# Sheet1.net
KiCad netlist of a schematic drawn in Altium Designer
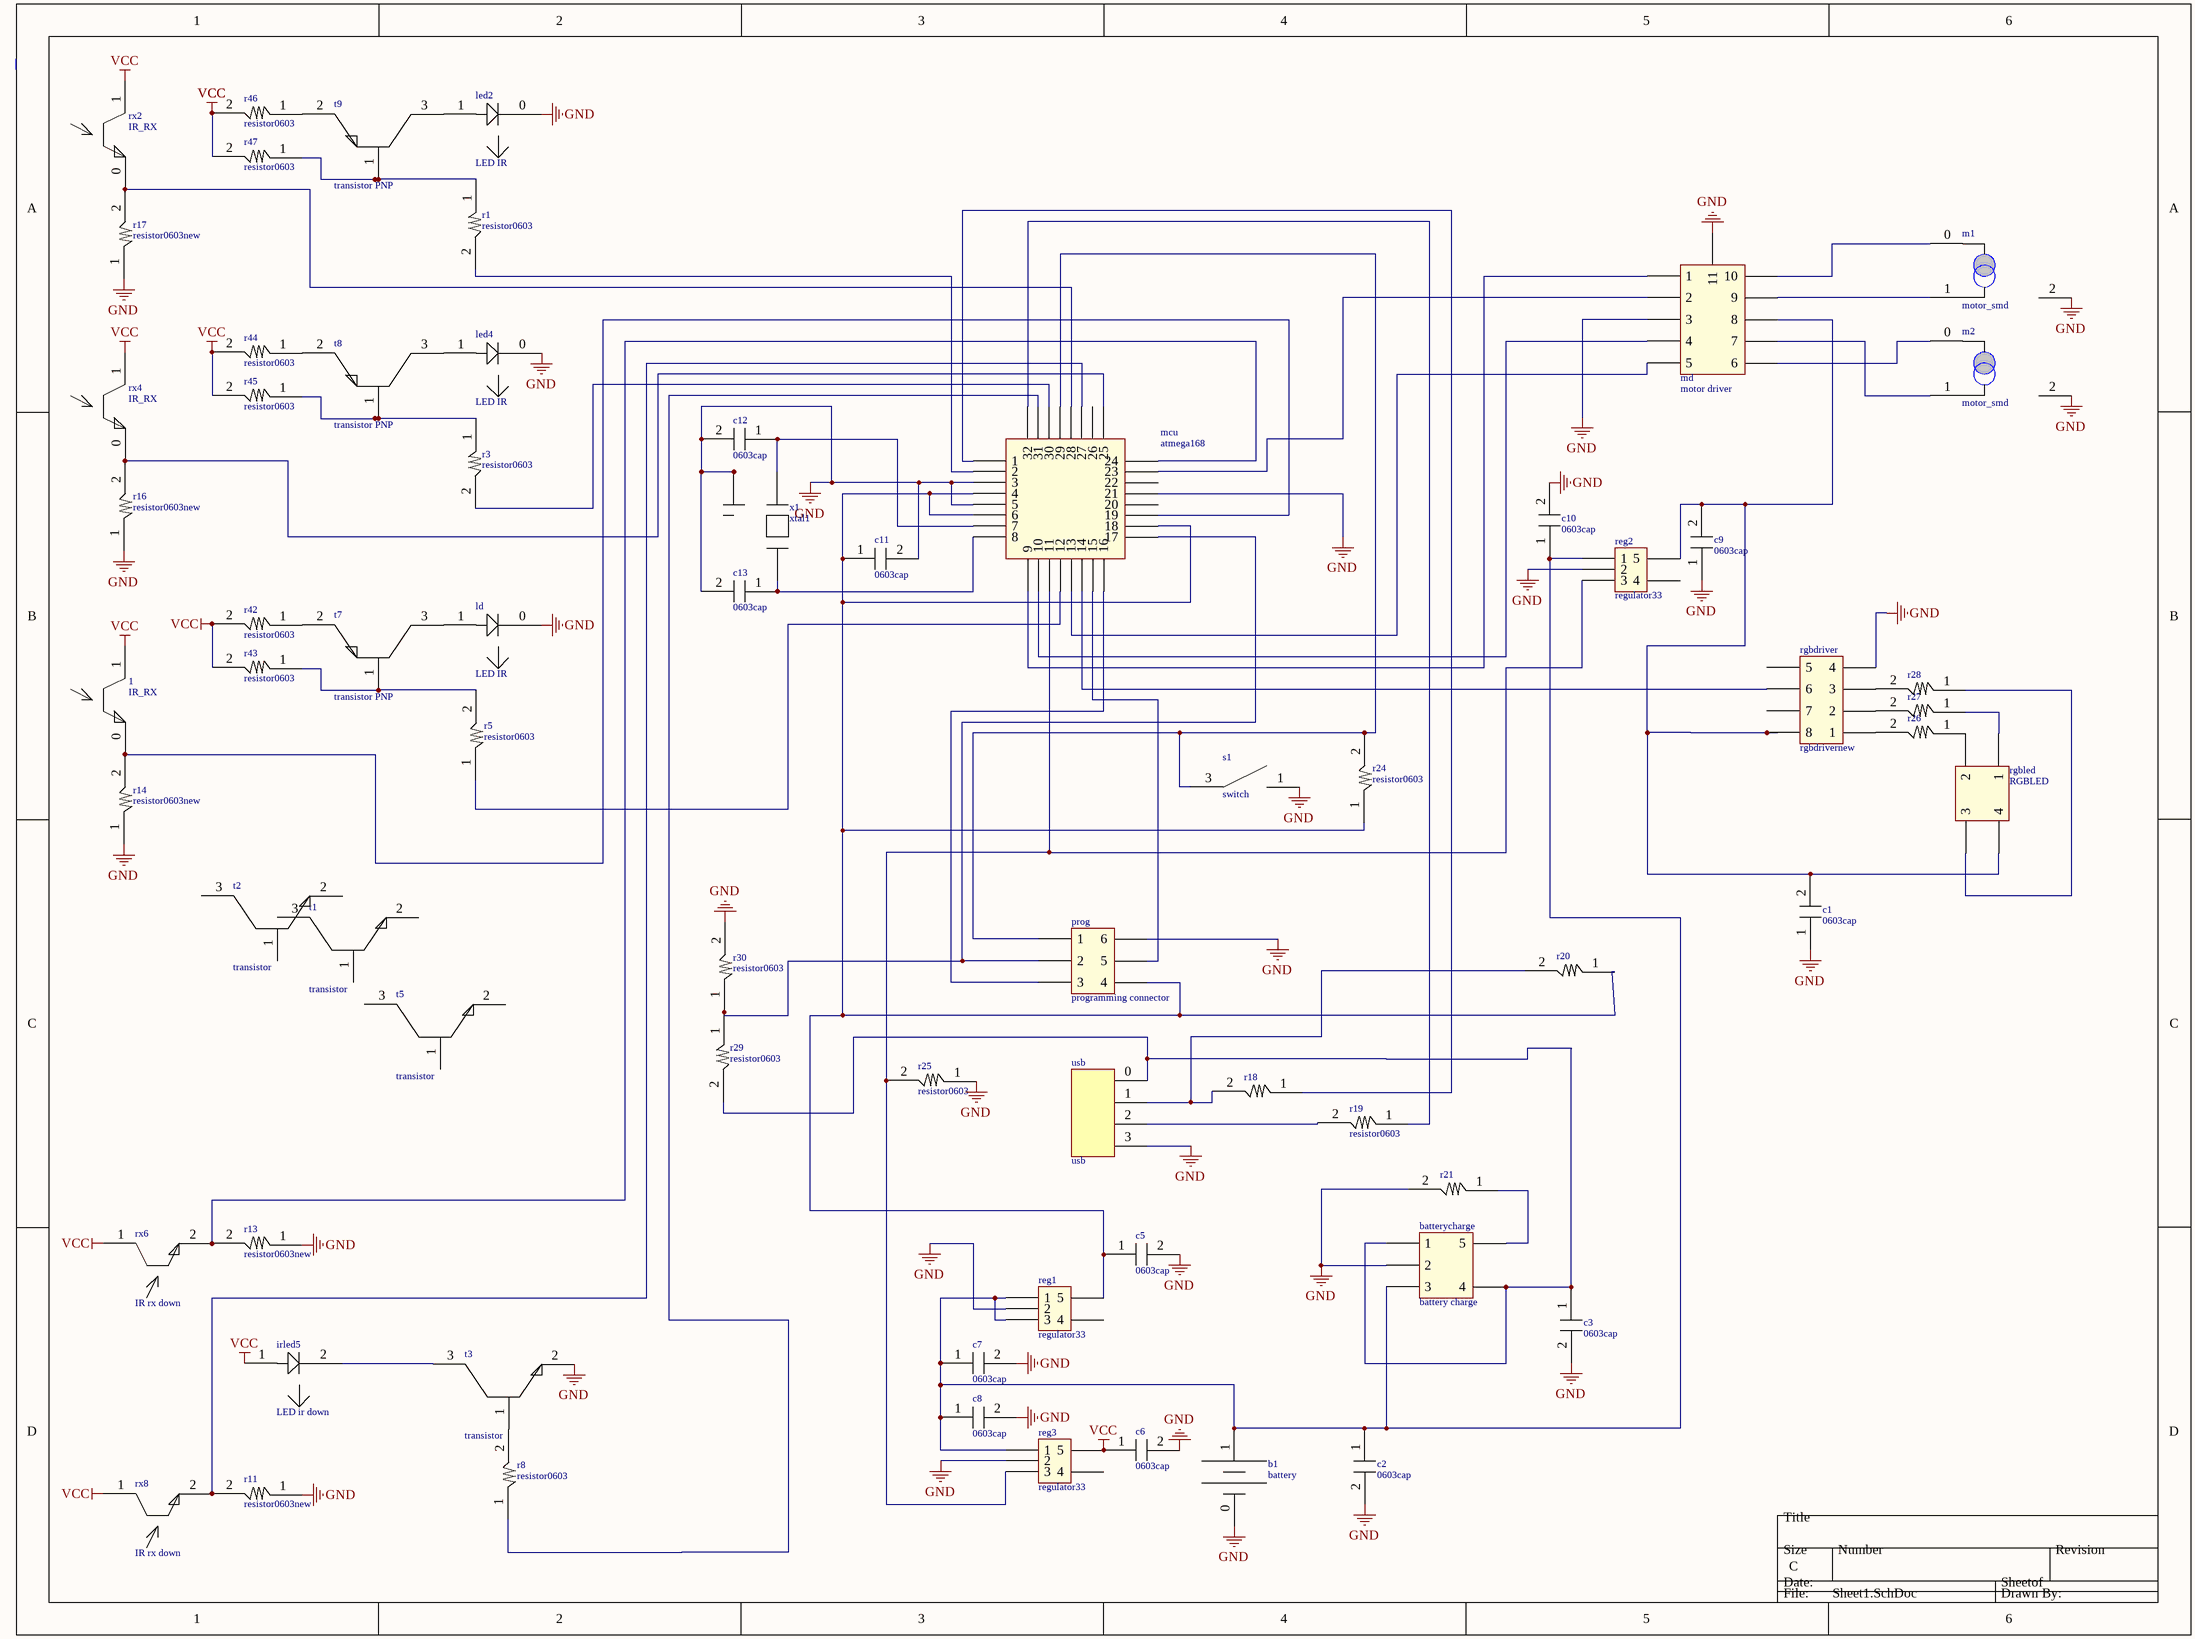
[diagram p0: Sheet1.SchDoc]

(export (version "E")
  (design (tool "Eeschema 10.0.6"))
  (components
    (comp (ref "1") (value "IR_RX") (footprint "ir sensor") (libsource (lib "Schlib1") (part "IR_RX")))
    (comp (ref "b1") (value "battery") (footprint "battery") (libsource (lib "Schlib1") (part "battery")))
    (comp (ref "batterycharge")
      (value "battery charge")
      (footprint "Battery charger")
      (libsource (lib "Schlib1") (part "battery charge"))
    )
    (comp (ref "c1") (value "0603cap") (footprint "0603new") (libsource (lib "Schlib1") (part "0603cap")))
    (comp (ref "c2") (value "0603cap") (footprint "0603new") (libsource (lib "Schlib1") (part "0603cap")))
    (comp (ref "c3") (value "0603cap") (footprint "0603new") (libsource (lib "Schlib1") (part "0603cap")))
    (comp (ref "c5") (value "0603cap") (footprint "0603new") (libsource (lib "Schlib1") (part "0603cap")))
    (comp (ref "c6") (value "0603cap") (footprint "0603new") (libsource (lib "Schlib1") (part "0603cap")))
    (comp (ref "c7") (value "0603cap") (footprint "0603new") (libsource (lib "Schlib1") (part "0603cap")))
    (comp (ref "c8") (value "0603cap") (footprint "0603new") (libsource (lib "Schlib1") (part "0603cap")))
    (comp (ref "c9") (value "0603cap") (footprint "0603new") (libsource (lib "Schlib1") (part "0603cap")))
    (comp (ref "c10") (value "0603cap") (footprint "0603new") (libsource (lib "Schlib1") (part "0603cap")))
    (comp (ref "c11") (value "0603cap") (footprint "0603new") (libsource (lib "Schlib1") (part "0603cap")))
    (comp (ref "c12") (value "0603cap") (footprint "0603new") (libsource (lib "Schlib1") (part "0603cap")))
    (comp (ref "c13") (value "0603cap") (footprint "0603new") (libsource (lib "Schlib1") (part "0603cap")))
    (comp (ref "irled5")
      (value "LED ir down")
      (footprint "irdown")
      (libsource (lib "Schlib1") (part "LED ir down"))
    )
    (comp (ref "ld") (value "LED IR") (footprint "ir led") (libsource (lib "Schlib1") (part "LED IR")))
    (comp (ref "led2") (value "LED IR") (footprint "ir led") (libsource (lib "Schlib1") (part "LED IR")))
    (comp (ref "led4") (value "LED IR") (footprint "ir led") (libsource (lib "Schlib1") (part "LED IR")))
    (comp (ref "m1") (value "motor_smd") (footprint "motor") (libsource (lib "Schlib1") (part "motor_smd")))
    (comp (ref "m2") (value "motor_smd") (footprint "motor") (libsource (lib "Schlib1") (part "motor_smd")))
    (comp (ref "mcu")
      (value "atmega168")
      (footprint "32pintqfp")
      (libsource (lib "Schlib1") (part "atmega168"))
    )
    (comp (ref "md")
      (value "motor driver")
      (footprint "motor driver")
      (libsource (lib "Schlib1") (part "motor driver"))
    )
    (comp (ref "prog")
      (value "programming connector")
      (footprint "Program connector")
      (libsource (lib "Schlib1") (part "programming connector"))
    )
    (comp (ref "r1")
      (value "resistor0603")
      (footprint "0603new")
      (libsource (lib "Schlib1") (part "resistor0603"))
    )
    (comp (ref "r3")
      (value "resistor0603")
      (footprint "0603new")
      (libsource (lib "Schlib1") (part "resistor0603"))
    )
    (comp (ref "r5")
      (value "resistor0603")
      (footprint "0603new")
      (libsource (lib "Schlib1") (part "resistor0603"))
    )
    (comp (ref "r8")
      (value "resistor0603")
      (footprint "0603new")
      (libsource (lib "Schlib1") (part "resistor0603"))
    )
    (comp (ref "r11")
      (value "resistor0603new")
      (footprint "0603new")
      (libsource (lib "Schlib1") (part "resistor0603new"))
    )
    (comp (ref "r13")
      (value "resistor0603new")
      (footprint "0603new")
      (libsource (lib "") (part "resistor0603new_1"))
    )
    (comp (ref "r14")
      (value "resistor0603new")
      (footprint "0603new")
      (libsource (lib "") (part "resistor0603new_1"))
    )
    (comp (ref "r16")
      (value "resistor0603new")
      (footprint "0603new")
      (libsource (lib "") (part "resistor0603new_1"))
    )
    (comp (ref "r17")
      (value "resistor0603new")
      (footprint "0603new")
      (libsource (lib "") (part "resistor0603new_1"))
    )
    (comp (ref "r18")
      (value "resistor0603")
      (footprint "0603new")
      (libsource (lib "Schlib1") (part "resistor0603"))
    )
    (comp (ref "r19")
      (value "resistor0603")
      (footprint "0603new")
      (libsource (lib "Schlib1") (part "resistor0603"))
    )
    (comp (ref "r20")
      (value "resistor0603")
      (footprint "0603new")
      (libsource (lib "Schlib1") (part "resistor0603"))
    )
    (comp (ref "r21")
      (value "resistor0603")
      (footprint "0603new")
      (libsource (lib "Schlib1") (part "resistor0603"))
    )
    (comp (ref "r24")
      (value "resistor0603")
      (footprint "0603new")
      (libsource (lib "Schlib1") (part "resistor0603"))
    )
    (comp (ref "r25")
      (value "resistor0603")
      (footprint "0603new")
      (libsource (lib "Schlib1") (part "resistor0603"))
    )
    (comp (ref "r26")
      (value "resistor0603")
      (footprint "0603new")
      (libsource (lib "Schlib1") (part "resistor0603"))
    )
    (comp (ref "r27")
      (value "resistor0603")
      (footprint "0603new")
      (libsource (lib "Schlib1") (part "resistor0603"))
    )
    (comp (ref "r28")
      (value "resistor0603")
      (footprint "0603new")
      (libsource (lib "Schlib1") (part "resistor0603"))
    )
    (comp (ref "r29")
      (value "resistor0603")
      (footprint "0603new")
      (libsource (lib "Schlib1") (part "resistor0603"))
    )
    (comp (ref "r30")
      (value "resistor0603")
      (footprint "0603new")
      (libsource (lib "Schlib1") (part "resistor0603"))
    )
    (comp (ref "r42")
      (value "resistor0603")
      (footprint "0603new")
      (libsource (lib "Schlib1") (part "resistor0603"))
    )
    (comp (ref "r43")
      (value "resistor0603")
      (footprint "0603new")
      (libsource (lib "Schlib1") (part "resistor0603"))
    )
    (comp (ref "r44")
      (value "resistor0603")
      (footprint "0603new")
      (libsource (lib "Schlib1") (part "resistor0603"))
    )
    (comp (ref "r45")
      (value "resistor0603")
      (footprint "0603new")
      (libsource (lib "Schlib1") (part "resistor0603"))
    )
    (comp (ref "r46")
      (value "resistor0603")
      (footprint "0603new")
      (libsource (lib "Schlib1") (part "resistor0603"))
    )
    (comp (ref "r47")
      (value "resistor0603")
      (footprint "0603new")
      (libsource (lib "Schlib1") (part "resistor0603"))
    )
    (comp (ref "reg1")
      (value "regulator33")
      (footprint "regulator")
      (libsource (lib "Schlib1") (part "regulator33"))
    )
    (comp (ref "reg2")
      (value "regulator33")
      (footprint "regulator")
      (libsource (lib "Schlib1") (part "regulator33"))
    )
    (comp (ref "reg3")
      (value "regulator33")
      (footprint "regulator")
      (libsource (lib "Schlib1") (part "regulator33"))
    )
    (comp (ref "rgbdriver")
      (value "rgbdrivernew")
      (footprint "RGBdrivernew")
      (description "rgbdrver")
      (libsource (lib "Schlib1") (part "rgbdrivernew"))
    )
    (comp (ref "rgbled") (value "RGBLED") (footprint "rgbled") (libsource (lib "Schlib1") (part "RGBLED")))
    (comp (ref "rx2") (value "IR_RX") (footprint "ir sensor") (libsource (lib "Schlib1") (part "IR_RX")))
    (comp (ref "rx4") (value "IR_RX") (footprint "ir sensor") (libsource (lib "Schlib1") (part "IR_RX")))
    (comp (ref "rx6")
      (value "IR rx down")
      (footprint "irdown")
      (libsource (lib "Schlib1") (part "IR rx down"))
    )
    (comp (ref "rx8")
      (value "IR rx down")
      (footprint "irdown")
      (libsource (lib "Schlib1") (part "IR rx down"))
    )
    (comp (ref "s1") (value "switch") (footprint "switch") (libsource (lib "Schlib1") (part "switch")))
    (comp (ref "t1")
      (value "transistor")
      (footprint "transistor")
      (libsource (lib "Schlib1") (part "transistor"))
    )
    (comp (ref "t2")
      (value "transistor")
      (footprint "transistor")
      (libsource (lib "Schlib1") (part "transistor"))
    )
    (comp (ref "t3")
      (value "transistor")
      (footprint "transistor")
      (libsource (lib "Schlib1") (part "transistor"))
    )
    (comp (ref "t5")
      (value "transistor")
      (footprint "transistor")
      (libsource (lib "Schlib1") (part "transistor"))
    )
    (comp (ref "t7")
      (value "transistor PNP")
      (footprint "transistor")
      (libsource (lib "Schlib1") (part "transistor PNP"))
    )
    (comp (ref "t8")
      (value "transistor PNP")
      (footprint "transistor")
      (libsource (lib "Schlib1") (part "transistor PNP"))
    )
    (comp (ref "t9")
      (value "transistor PNP")
      (footprint "transistor")
      (libsource (lib "Schlib1") (part "transistor PNP"))
    )
    (comp (ref "usb") (value "usb") (footprint "usb") (libsource (lib "Schlib1") (part "usb")))
    (comp (ref "x1")
      (value "xtal1")
      (footprint "xtal1")
      (description "xtal")
      (libsource (lib "Schlib1") (part "xtal"))
    )
  )
  (nets
    (net (code "1") (name "GND") (class "Default")
      (node (ref "b1") (pin "0") (pinfunction "0_0") (pintype "passive"))
      (node (ref "batterycharge") (pin "2") (pinfunction "2_2") (pintype "passive"))
      (node (ref "c1") (pin "1") (pinfunction "1_1") (pintype "passive"))
      (node (ref "c10") (pin "2") (pinfunction "2_2") (pintype "passive"))
      (node (ref "c11") (pin "2") (pinfunction "2_2") (pintype "passive"))
      (node (ref "c12") (pin "2") (pinfunction "2_2") (pintype "passive"))
      (node (ref "c13") (pin "2") (pinfunction "2_2") (pintype "passive"))
      (node (ref "c2") (pin "2") (pinfunction "2_2") (pintype "passive"))
      (node (ref "c3") (pin "2") (pinfunction "2_2") (pintype "passive"))
      (node (ref "c5") (pin "2") (pinfunction "2_2") (pintype "passive"))
      (node (ref "c6") (pin "2") (pinfunction "2_2") (pintype "passive"))
      (node (ref "c7") (pin "2") (pinfunction "2_2") (pintype "passive"))
      (node (ref "c8") (pin "2") (pinfunction "2_2") (pintype "passive"))
      (node (ref "c9") (pin "1") (pinfunction "1_1") (pintype "passive"))
      (node (ref "ld") (pin "0") (pinfunction "0_0") (pintype "passive"))
      (node (ref "led2") (pin "0") (pinfunction "0_0") (pintype "passive"))
      (node (ref "led4") (pin "0") (pinfunction "0_0") (pintype "passive"))
      (node (ref "m1") (pin "2") (pinfunction "2_2") (pintype "passive"))
      (node (ref "m2") (pin "2") (pinfunction "2_2") (pintype "passive"))
      (node (ref "mcu") (pin "21") (pinfunction "21_21") (pintype "passive"))
      (node (ref "mcu") (pin "3") (pinfunction "3_3") (pintype "passive"))
      (node (ref "mcu") (pin "5") (pinfunction "5_5") (pintype "passive"))
      (node (ref "md") (pin "11") (pinfunction "11_11") (pintype "passive"))
      (node (ref "md") (pin "3") (pinfunction "3_3") (pintype "passive"))
      (node (ref "prog") (pin "6") (pinfunction "6_6") (pintype "passive"))
      (node (ref "r11") (pin "1") (pinfunction "1_1") (pintype "passive"))
      (node (ref "r13") (pin "1") (pinfunction "1_1") (pintype "passive"))
      (node (ref "r14") (pin "1") (pinfunction "1_1") (pintype "passive"))
      (node (ref "r16") (pin "1") (pinfunction "1_1") (pintype "passive"))
      (node (ref "r17") (pin "1") (pinfunction "1_1") (pintype "passive"))
      (node (ref "r21") (pin "2") (pinfunction "2_2") (pintype "passive"))
      (node (ref "r25") (pin "1") (pinfunction "1_1") (pintype "passive"))
      (node (ref "r30") (pin "2") (pinfunction "2_2") (pintype "passive"))
      (node (ref "reg1") (pin "2") (pinfunction "2_2") (pintype "passive"))
      (node (ref "reg2") (pin "2") (pinfunction "2_2") (pintype "passive"))
      (node (ref "reg3") (pin "2") (pinfunction "2_2") (pintype "passive"))
      (node (ref "rgbdriver") (pin "4") (pinfunction "4_4") (pintype "passive"))
      (node (ref "s1") (pin "1") (pinfunction "1_1") (pintype "passive"))
      (node (ref "t3") (pin "2") (pinfunction "2_2") (pintype "passive"))
      (node (ref "usb") (pin "3") (pinfunction "3_3") (pintype "passive"))
      (node (ref "x1") (pin "2") (pinfunction "2_2") (pintype "passive"))
      (node (ref "x1") (pin "4") (pinfunction "4_4") (pintype "passive"))
    )
    (net (code "2") (name "Net-(1-Pad0)") (class "Default")
      (node (ref "1") (pin "0") (pinfunction "0_0") (pintype "passive"))
      (node (ref "mcu") (pin "19") (pinfunction "19_19") (pintype "passive"))
      (node (ref "r14") (pin "2") (pinfunction "2_2") (pintype "passive"))
    )
    (net (code "3") (name "Net-(b1-Pad1)") (class "Default")
      (node (ref "b1") (pin "1") (pinfunction "1_1") (pintype "passive"))
      (node (ref "b1") (pin "2") (pinfunction "2_2") (pintype "passive"))
      (node (ref "batterycharge") (pin "3") (pinfunction "3_3") (pintype "passive"))
      (node (ref "c10") (pin "1") (pinfunction "1_1") (pintype "passive"))
      (node (ref "c2") (pin "1") (pinfunction "1_1") (pintype "passive"))
      (node (ref "c7") (pin "1") (pinfunction "1_1") (pintype "passive"))
      (node (ref "c8") (pin "1") (pinfunction "1_1") (pintype "passive"))
      (node (ref "reg1") (pin "1") (pinfunction "1_1") (pintype "passive"))
      (node (ref "reg1") (pin "3") (pinfunction "3_3") (pintype "passive"))
      (node (ref "reg2") (pin "1") (pinfunction "1_1") (pintype "passive"))
      (node (ref "reg3") (pin "1") (pinfunction "1_1") (pintype "passive"))
    )
    (net (code "4") (name "Net-(batterycharge-Pad1)") (class "Default")
      (node (ref "batterycharge") (pin "1") (pinfunction "1_1") (pintype "passive"))
      (node (ref "batterycharge") (pin "4") (pinfunction "4_4") (pintype "passive"))
      (node (ref "c3") (pin "1") (pinfunction "1_1") (pintype "passive"))
      (node (ref "r29") (pin "2") (pinfunction "2_2") (pintype "passive"))
      (node (ref "usb") (pin "0") (pinfunction "0_0") (pintype "passive"))
    )
    (net (code "5") (name "Net-(batterycharge-Pad5)") (class "Default")
      (node (ref "batterycharge") (pin "5") (pinfunction "5_5") (pintype "passive"))
      (node (ref "r21") (pin "1") (pinfunction "1_1") (pintype "passive"))
    )
    (net (code "6") (name "Net-(c1-Pad2)") (class "Default")
      (node (ref "c1") (pin "2") (pinfunction "2_2") (pintype "passive"))
      (node (ref "c9") (pin "2") (pinfunction "2_2") (pintype "passive"))
      (node (ref "md") (pin "8") (pinfunction "8_8") (pintype "passive"))
      (node (ref "reg2") (pin "5") (pinfunction "5_5") (pintype "passive"))
      (node (ref "rgbdriver") (pin "8") (pinfunction "8_8") (pintype "passive"))
      (node (ref "rgbled") (pin "4") (pinfunction "4_4") (pintype "passive"))
    )
    (net (code "7") (name "Net-(c11-Pad1)") (class "Default")
      (node (ref "c11") (pin "1") (pinfunction "1_1") (pintype "passive"))
      (node (ref "c5") (pin "1") (pinfunction "1_1") (pintype "passive"))
      (node (ref "mcu") (pin "18") (pinfunction "18_18") (pintype "passive"))
      (node (ref "mcu") (pin "4") (pinfunction "4_4") (pintype "passive"))
      (node (ref "mcu") (pin "6") (pinfunction "6_6") (pintype "passive"))
      (node (ref "prog") (pin "4") (pinfunction "4_4") (pintype "passive"))
      (node (ref "r20") (pin "1") (pinfunction "1_1") (pintype "passive"))
      (node (ref "r24") (pin "1") (pinfunction "1_1") (pintype "passive"))
      (node (ref "reg1") (pin "5") (pinfunction "5_5") (pintype "passive"))
    )
    (net (code "8") (name "Net-(c12-Pad1)") (class "Default")
      (node (ref "c12") (pin "1") (pinfunction "1_1") (pintype "passive"))
      (node (ref "mcu") (pin "7") (pinfunction "7_7") (pintype "passive"))
      (node (ref "x1") (pin "1") (pinfunction "1_1") (pintype "passive"))
    )
    (net (code "9") (name "Net-(c13-Pad1)") (class "Default")
      (node (ref "c13") (pin "1") (pinfunction "1_1") (pintype "passive"))
      (node (ref "mcu") (pin "8") (pinfunction "8_8") (pintype "passive"))
      (node (ref "x1") (pin "3") (pinfunction "3_3") (pintype "passive"))
    )
    (net (code "10") (name "Net-(irled5-Pad2)") (class "Default")
      (node (ref "irled5") (pin "2") (pinfunction "2_2") (pintype "passive"))
      (node (ref "t3") (pin "3") (pinfunction "3_3") (pintype "passive"))
    )
    (net (code "11") (name "Net-(ld-Pad1)") (class "Default")
      (node (ref "ld") (pin "1") (pinfunction "1_1") (pintype "passive"))
      (node (ref "t7") (pin "3") (pinfunction "3_3") (pintype "passive"))
    )
    (net (code "12") (name "Net-(led2-Pad1)") (class "Default")
      (node (ref "led2") (pin "1") (pinfunction "1_1") (pintype "passive"))
      (node (ref "t9") (pin "3") (pinfunction "3_3") (pintype "passive"))
    )
    (net (code "13") (name "Net-(led4-Pad1)") (class "Default")
      (node (ref "led4") (pin "1") (pinfunction "1_1") (pintype "passive"))
      (node (ref "t8") (pin "3") (pinfunction "3_3") (pintype "passive"))
    )
    (net (code "14") (name "Net-(m1-Pad0)") (class "Default")
      (node (ref "m1") (pin "0") (pinfunction "0_0") (pintype "passive"))
      (node (ref "md") (pin "10") (pinfunction "10_10") (pintype "passive"))
    )
    (net (code "15") (name "Net-(m1-Pad1)") (class "Default")
      (node (ref "m1") (pin "1") (pinfunction "1_1") (pintype "passive"))
      (node (ref "md") (pin "9") (pinfunction "9_9") (pintype "passive"))
    )
    (net (code "16") (name "Net-(m2-Pad0)") (class "Default")
      (node (ref "m2") (pin "0") (pinfunction "0_0") (pintype "passive"))
      (node (ref "md") (pin "6") (pinfunction "6_6") (pintype "passive"))
    )
    (net (code "17") (name "Net-(m2-Pad1)") (class "Default")
      (node (ref "m2") (pin "1") (pinfunction "1_1") (pintype "passive"))
      (node (ref "md") (pin "7") (pinfunction "7_7") (pintype "passive"))
    )
    (net (code "18") (name "Net-(mcu-Pad1)") (class "Default")
      (node (ref "mcu") (pin "1") (pinfunction "1_1") (pintype "passive"))
      (node (ref "r18") (pin "1") (pinfunction "1_1") (pintype "passive"))
    )
    (net (code "19") (name "Net-(mcu-Pad2)") (class "Default")
      (node (ref "mcu") (pin "2") (pinfunction "2_2") (pintype "passive"))
      (node (ref "r1") (pin "2") (pinfunction "2_2") (pintype "passive"))
    )
    (net (code "20") (name "Net-(mcu-Pad9)") (class "Default")
      (node (ref "mcu") (pin "9") (pinfunction "9_9") (pintype "passive"))
      (node (ref "md") (pin "1") (pinfunction "1_1") (pintype "passive"))
    )
    (net (code "21") (name "Net-(mcu-Pad10)") (class "Default")
      (node (ref "mcu") (pin "10") (pinfunction "10_10") (pintype "passive"))
      (node (ref "md") (pin "4") (pinfunction "4_4") (pintype "passive"))
    )
    (net (code "22") (name "Net-(mcu-Pad11)") (class "Default")
      (node (ref "mcu") (pin "11") (pinfunction "11_11") (pintype "passive"))
      (node (ref "r25") (pin "2") (pinfunction "2_2") (pintype "passive"))
      (node (ref "reg2") (pin "3") (pinfunction "3_3") (pintype "passive"))
      (node (ref "reg3") (pin "3") (pinfunction "3_3") (pintype "passive"))
    )
    (net (code "23") (name "Net-(mcu-Pad12)") (class "Default")
      (node (ref "mcu") (pin "12") (pinfunction "12_12") (pintype "passive"))
      (node (ref "r5") (pin "1") (pinfunction "1_1") (pintype "passive"))
    )
    (net (code "24") (name "Net-(mcu-Pad13)") (class "Default")
      (node (ref "mcu") (pin "13") (pinfunction "13_13") (pintype "passive"))
      (node (ref "md") (pin "5") (pinfunction "5_5") (pintype "passive"))
    )
    (net (code "25") (name "Net-(mcu-Pad14)") (class "Default")
      (node (ref "mcu") (pin "14") (pinfunction "14_14") (pintype "passive"))
      (node (ref "rgbdriver") (pin "6") (pinfunction "6_6") (pintype "passive"))
    )
    (net (code "26") (name "Net-(mcu-Pad15)") (class "Default")
      (node (ref "mcu") (pin "15") (pinfunction "15_15") (pintype "passive"))
      (node (ref "prog") (pin "5") (pinfunction "5_5") (pintype "passive"))
    )
    (net (code "27") (name "Net-(mcu-Pad16)") (class "Default")
      (node (ref "mcu") (pin "16") (pinfunction "16_16") (pintype "passive"))
      (node (ref "prog") (pin "3") (pinfunction "3_3") (pintype "passive"))
    )
    (net (code "28") (name "Net-(mcu-Pad17)") (class "Default")
      (node (ref "mcu") (pin "17") (pinfunction "17_17") (pintype "passive"))
      (node (ref "prog") (pin "2") (pinfunction "2_2") (pintype "passive"))
      (node (ref "r29") (pin "1") (pinfunction "1_1") (pintype "passive"))
      (node (ref "r30") (pin "1") (pinfunction "1_1") (pintype "passive"))
    )
    (net (code "29") (name "Net-(mcu-Pad23)") (class "Default")
      (node (ref "mcu") (pin "23") (pinfunction "23_23") (pintype "passive"))
      (node (ref "md") (pin "2") (pinfunction "2_2") (pintype "passive"))
    )
    (net (code "30") (name "Net-(mcu-Pad24)") (class "Default")
      (node (ref "mcu") (pin "24") (pinfunction "24_24") (pintype "passive"))
      (node (ref "r13") (pin "2") (pinfunction "2_2") (pintype "passive"))
      (node (ref "rx6") (pin "2") (pinfunction "2_2") (pintype "passive"))
    )
    (net (code "31") (name "Net-(mcu-Pad25)") (class "Default")
      (node (ref "mcu") (pin "25") (pinfunction "25_25") (pintype "passive"))
      (node (ref "r16") (pin "2") (pinfunction "2_2") (pintype "passive"))
      (node (ref "rx4") (pin "0") (pinfunction "0_0") (pintype "passive"))
    )
    (net (code "32") (name "Net-(mcu-Pad27)") (class "Default")
      (node (ref "mcu") (pin "27") (pinfunction "27_27") (pintype "passive"))
      (node (ref "r11") (pin "2") (pinfunction "2_2") (pintype "passive"))
      (node (ref "rx8") (pin "2") (pinfunction "2_2") (pintype "passive"))
    )
    (net (code "33") (name "Net-(mcu-Pad28)") (class "Default")
      (node (ref "mcu") (pin "28") (pinfunction "28_28") (pintype "passive"))
      (node (ref "r17") (pin "2") (pinfunction "2_2") (pintype "passive"))
      (node (ref "rx2") (pin "0") (pinfunction "0_0") (pintype "passive"))
    )
    (net (code "34") (name "Net-(mcu-Pad29)") (class "Default")
      (node (ref "mcu") (pin "29") (pinfunction "29_29") (pintype "passive"))
      (node (ref "prog") (pin "1") (pinfunction "1_1") (pintype "passive"))
      (node (ref "r24") (pin "2") (pinfunction "2_2") (pintype "passive"))
      (node (ref "s1") (pin "3") (pinfunction "3_3") (pintype "passive"))
    )
    (net (code "35") (name "Net-(mcu-Pad30)") (class "Default")
      (node (ref "mcu") (pin "30") (pinfunction "30_30") (pintype "passive"))
      (node (ref "r3") (pin "2") (pinfunction "2_2") (pintype "passive"))
    )
    (net (code "36") (name "Net-(mcu-Pad31)") (class "Default")
      (node (ref "mcu") (pin "31") (pinfunction "31_31") (pintype "passive"))
      (node (ref "r8") (pin "1") (pinfunction "1_1") (pintype "passive"))
    )
    (net (code "37") (name "Net-(mcu-Pad32)") (class "Default")
      (node (ref "mcu") (pin "32") (pinfunction "32_32") (pintype "passive"))
      (node (ref "r19") (pin "1") (pinfunction "1_1") (pintype "passive"))
    )
    (net (code "38") (name "Net-(r1-Pad1)") (class "Default")
      (node (ref "r1") (pin "1") (pinfunction "1_1") (pintype "passive"))
      (node (ref "r47") (pin "1") (pinfunction "1_1") (pintype "passive"))
      (node (ref "t9") (pin "1") (pinfunction "1_1") (pintype "passive"))
    )
    (net (code "39") (name "Net-(r3-Pad1)") (class "Default")
      (node (ref "r3") (pin "1") (pinfunction "1_1") (pintype "passive"))
      (node (ref "r45") (pin "1") (pinfunction "1_1") (pintype "passive"))
      (node (ref "t8") (pin "1") (pinfunction "1_1") (pintype "passive"))
    )
    (net (code "40") (name "Net-(r8-Pad2)") (class "Default")
      (node (ref "r8") (pin "2") (pinfunction "2_2") (pintype "passive"))
      (node (ref "t3") (pin "1") (pinfunction "1_1") (pintype "passive"))
    )
    (net (code "41") (name "Net-(r18-Pad2)") (class "Default")
      (node (ref "r18") (pin "2") (pinfunction "2_2") (pintype "passive"))
      (node (ref "r20") (pin "2") (pinfunction "2_2") (pintype "passive"))
      (node (ref "usb") (pin "1") (pinfunction "1_1") (pintype "passive"))
    )
    (net (code "42") (name "Net-(r19-Pad2)") (class "Default")
      (node (ref "r19") (pin "2") (pinfunction "2_2") (pintype "passive"))
      (node (ref "usb") (pin "2") (pinfunction "2_2") (pintype "passive"))
    )
    (net (code "43") (name "Net-(r26-Pad1)") (class "Default")
      (node (ref "r26") (pin "1") (pinfunction "1_1") (pintype "passive"))
      (node (ref "rgbled") (pin "2") (pinfunction "2_2") (pintype "passive"))
    )
    (net (code "44") (name "Net-(r26-Pad2)") (class "Default")
      (node (ref "r26") (pin "2") (pinfunction "2_2") (pintype "passive"))
      (node (ref "rgbdriver") (pin "1") (pinfunction "1_1") (pintype "passive"))
    )
    (net (code "45") (name "Net-(r27-Pad1)") (class "Default")
      (node (ref "r27") (pin "1") (pinfunction "1_1") (pintype "passive"))
      (node (ref "rgbled") (pin "1") (pinfunction "1_1") (pintype "passive"))
    )
    (net (code "46") (name "Net-(r27-Pad2)") (class "Default")
      (node (ref "r27") (pin "2") (pinfunction "2_2") (pintype "passive"))
      (node (ref "rgbdriver") (pin "2") (pinfunction "2_2") (pintype "passive"))
    )
    (net (code "47") (name "Net-(r28-Pad1)") (class "Default")
      (node (ref "r28") (pin "1") (pinfunction "1_1") (pintype "passive"))
      (node (ref "rgbled") (pin "3") (pinfunction "3_3") (pintype "passive"))
    )
    (net (code "48") (name "Net-(r28-Pad2)") (class "Default")
      (node (ref "r28") (pin "2") (pinfunction "2_2") (pintype "passive"))
      (node (ref "rgbdriver") (pin "3") (pinfunction "3_3") (pintype "passive"))
    )
    (net (code "49") (name "Net-(r42-Pad1)") (class "Default")
      (node (ref "r42") (pin "1") (pinfunction "1_1") (pintype "passive"))
      (node (ref "t7") (pin "2") (pinfunction "2_2") (pintype "passive"))
    )
    (net (code "50") (name "Net-(r43-Pad1)") (class "Default")
      (node (ref "r43") (pin "1") (pinfunction "1_1") (pintype "passive"))
      (node (ref "r5") (pin "2") (pinfunction "2_2") (pintype "passive"))
      (node (ref "t7") (pin "1") (pinfunction "1_1") (pintype "passive"))
    )
    (net (code "51") (name "Net-(r44-Pad1)") (class "Default")
      (node (ref "r44") (pin "1") (pinfunction "1_1") (pintype "passive"))
      (node (ref "t8") (pin "2") (pinfunction "2_2") (pintype "passive"))
    )
    (net (code "52") (name "Net-(r46-Pad1)") (class "Default")
      (node (ref "r46") (pin "1") (pinfunction "1_1") (pintype "passive"))
      (node (ref "t9") (pin "2") (pinfunction "2_2") (pintype "passive"))
    )
    (net (code "53") (name "VCC") (class "Default")
      (node (ref "1") (pin "1") (pinfunction "1_1") (pintype "passive"))
      (node (ref "c6") (pin "1") (pinfunction "1_1") (pintype "passive"))
      (node (ref "irled5") (pin "1") (pinfunction "1_1") (pintype "passive"))
      (node (ref "r42") (pin "2") (pinfunction "2_2") (pintype "passive"))
      (node (ref "r43") (pin "2") (pinfunction "2_2") (pintype "passive"))
      (node (ref "r44") (pin "2") (pinfunction "2_2") (pintype "passive"))
      (node (ref "r45") (pin "2") (pinfunction "2_2") (pintype "passive"))
      (node (ref "r46") (pin "2") (pinfunction "2_2") (pintype "passive"))
      (node (ref "r47") (pin "2") (pinfunction "2_2") (pintype "passive"))
      (node (ref "reg3") (pin "5") (pinfunction "5_5") (pintype "passive"))
      (node (ref "rx2") (pin "1") (pinfunction "1_1") (pintype "passive"))
      (node (ref "rx4") (pin "1") (pinfunction "1_1") (pintype "passive"))
      (node (ref "rx6") (pin "1") (pinfunction "1_1") (pintype "passive"))
      (node (ref "rx8") (pin "1") (pinfunction "1_1") (pintype "passive"))
    )
    (net (code "54") (name "unconnected-(mcu-Pad20)") (class "Default")
      (node (ref "mcu") (pin "20") (pinfunction "20_20") (pintype "passive"))
    )
    (net (code "55") (name "unconnected-(mcu-Pad22)") (class "Default")
      (node (ref "mcu") (pin "22") (pinfunction "22_22") (pintype "passive"))
    )
    (net (code "56") (name "unconnected-(mcu-Pad26)") (class "Default")
      (node (ref "mcu") (pin "26") (pinfunction "26_26") (pintype "passive"))
    )
    (net (code "57") (name "unconnected-(reg1-Pad4)") (class "Default")
      (node (ref "reg1") (pin "4") (pinfunction "4_4") (pintype "passive"))
    )
    (net (code "58") (name "unconnected-(reg2-Pad4)") (class "Default")
      (node (ref "reg2") (pin "4") (pinfunction "4_4") (pintype "passive"))
    )
    (net (code "59") (name "unconnected-(reg3-Pad4)") (class "Default")
      (node (ref "reg3") (pin "4") (pinfunction "4_4") (pintype "passive"))
    )
    (net (code "60") (name "unconnected-(rgbdriver-Pad5)") (class "Default")
      (node (ref "rgbdriver") (pin "5") (pinfunction "5_5") (pintype "passive"))
    )
    (net (code "61") (name "unconnected-(rgbdriver-Pad7)") (class "Default")
      (node (ref "rgbdriver") (pin "7") (pinfunction "7_7") (pintype "passive"))
    )
    (net (code "62") (name "unconnected-(t1-Pad1)") (class "Default")
      (node (ref "t1") (pin "1") (pinfunction "1_1") (pintype "passive"))
    )
    (net (code "63") (name "unconnected-(t1-Pad2)") (class "Default")
      (node (ref "t1") (pin "2") (pinfunction "2_2") (pintype "passive"))
    )
    (net (code "64") (name "unconnected-(t1-Pad3)") (class "Default")
      (node (ref "t1") (pin "3") (pinfunction "3_3") (pintype "passive"))
    )
    (net (code "65") (name "unconnected-(t2-Pad1)") (class "Default")
      (node (ref "t2") (pin "1") (pinfunction "1_1") (pintype "passive"))
    )
    (net (code "66") (name "unconnected-(t2-Pad2)") (class "Default")
      (node (ref "t2") (pin "2") (pinfunction "2_2") (pintype "passive"))
    )
    (net (code "67") (name "unconnected-(t2-Pad3)") (class "Default")
      (node (ref "t2") (pin "3") (pinfunction "3_3") (pintype "passive"))
    )
    (net (code "68") (name "unconnected-(t5-Pad1)") (class "Default")
      (node (ref "t5") (pin "1") (pinfunction "1_1") (pintype "passive"))
    )
    (net (code "69") (name "unconnected-(t5-Pad2)") (class "Default")
      (node (ref "t5") (pin "2") (pinfunction "2_2") (pintype "passive"))
    )
    (net (code "70") (name "unconnected-(t5-Pad3)") (class "Default")
      (node (ref "t5") (pin "3") (pinfunction "3_3") (pintype "passive"))
    )
  )
)
